# CH32V203C8U6-R0.net
KiCad netlist of a schematic drawn in Altium Designer
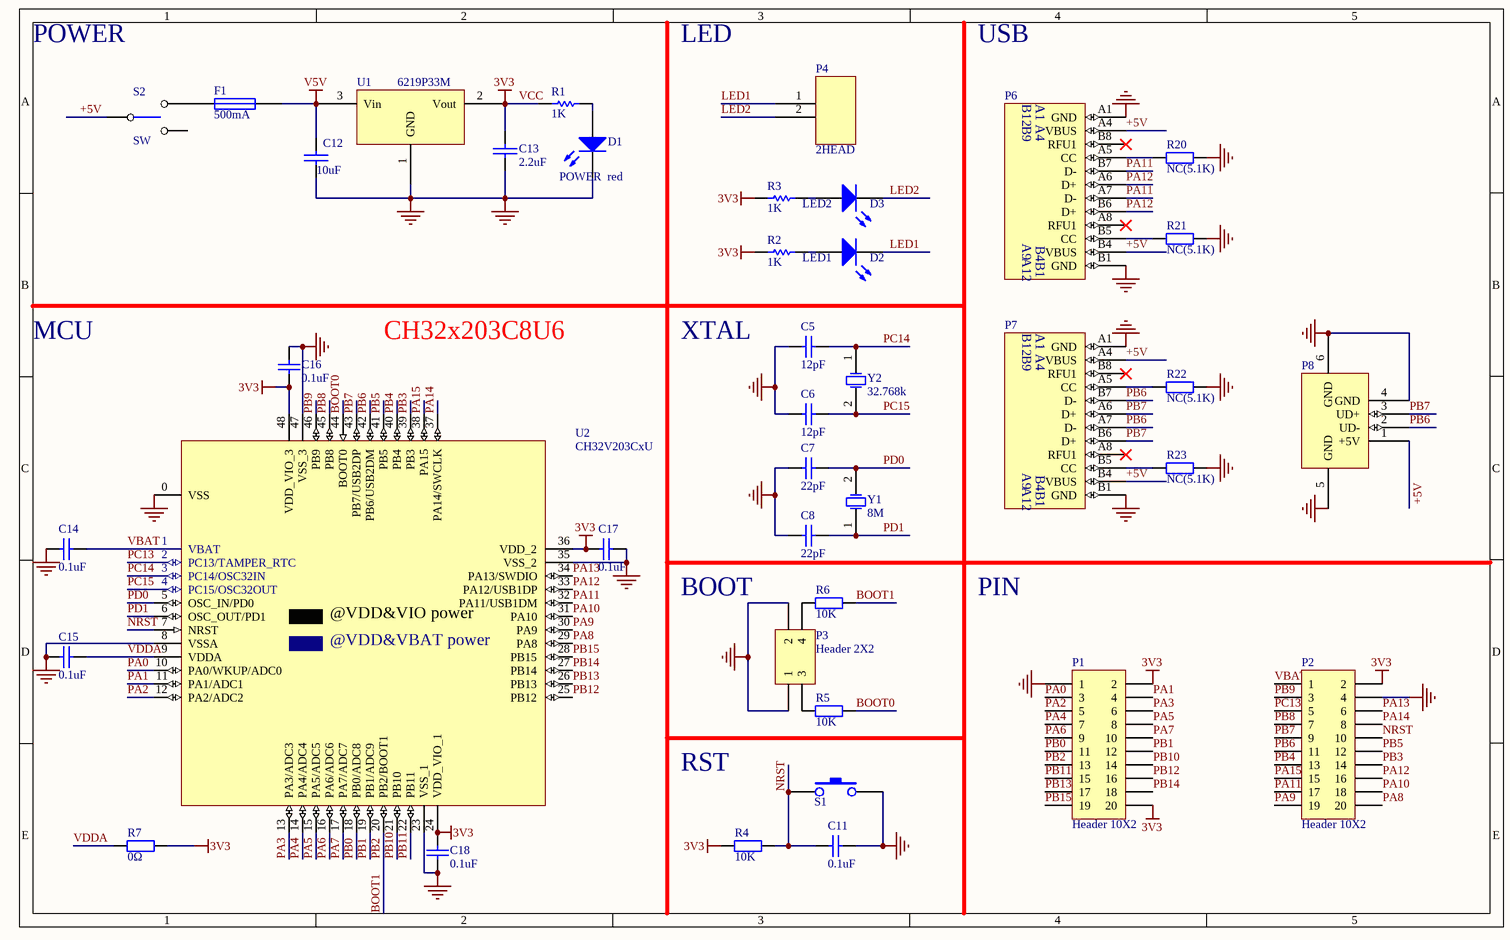
[diagram p0: CH32V203C8U6-R0.SchDoc]

(export (version "E")
  (design (tool "Eeschema 10.0.6"))
  (components
    (comp (ref "C5")
      (value "12pF")
      (footprint "0603")
      (description "Capacitor")
      (fields (field (name "PUBLISHER") "Altium Limited"))
      (libsource (lib "*") (part "Cap"))
    )
    (comp (ref "C6")
      (value "12pF")
      (footprint "0603")
      (description "Capacitor")
      (fields (field (name "PUBLISHER") "Altium Limited"))
      (libsource (lib "*") (part "Cap"))
    )
    (comp (ref "C7")
      (value "22pF")
      (footprint "0603")
      (description "Capacitor")
      (fields (field (name "PUBLISHER") "Altium Limited"))
      (libsource (lib "*") (part "Cap"))
    )
    (comp (ref "C8")
      (value "22pF")
      (footprint "0603")
      (description "Capacitor")
      (fields (field (name "PUBLISHER") "Altium Limited"))
      (libsource (lib "*") (part "Cap"))
    )
    (comp (ref "C11")
      (value "0.1uF")
      (footprint "0603")
      (description "Capacitor")
      (fields (field (name "PUBLISHER") "Altium Limited"))
      (libsource (lib "*") (part "Cap"))
    )
    (comp (ref "C12")
      (value "10uF")
      (footprint "3216")
      (description "Capacitor")
      (libsource (lib "*") (part "CAP"))
    )
    (comp (ref "C13")
      (value "2.2uF")
      (footprint "0603")
      (description "Capacitor")
      (libsource (lib "*") (part "CAP"))
    )
    (comp (ref "C14")
      (value "0.1uF")
      (footprint "0603")
      (description "Capacitor")
      (fields (field (name "PUBLISHER") "Altium Limited"))
      (libsource (lib "*") (part "Cap"))
    )
    (comp (ref "C15")
      (value "0.1uF")
      (footprint "0603")
      (description "Capacitor")
      (fields (field (name "PUBLISHER") "Altium Limited"))
      (libsource (lib "*") (part "Cap"))
    )
    (comp (ref "C16")
      (value "0.1uF")
      (footprint "0603")
      (description "Capacitor")
      (fields (field (name "PUBLISHER") "Altium Limited"))
      (libsource (lib "*") (part "Cap"))
    )
    (comp (ref "C17")
      (value "0.1uF")
      (footprint "0603")
      (description "Capacitor")
      (fields (field (name "PUBLISHER") "Altium Limited"))
      (libsource (lib "*") (part "Cap"))
    )
    (comp (ref "C18")
      (value "0.1uF")
      (footprint "0603")
      (description "Capacitor")
      (fields (field (name "PUBLISHER") "Altium Limited"))
      (libsource (lib "*") (part "Cap"))
    )
    (comp (ref "D1")
      (value "POWER  red")
      (footprint "0603L")
      (description "Typical INFRARED GaAs LED")
      (fields (field (name "PUBLISHER") "Altium Limited"))
      (libsource (lib "*") (part "LED0"))
    )
    (comp (ref "D2")
      (value "LED1")
      (footprint "0603L")
      (description "Typical INFRARED GaAs LED")
      (fields (field (name "PUBLISHER") "Altium Limited"))
      (libsource (lib "*") (part "LED0"))
    )
    (comp (ref "D3")
      (value "LED2")
      (footprint "0603L")
      (description "Typical INFRARED GaAs LED")
      (fields (field (name "PUBLISHER") "Altium Limited"))
      (libsource (lib "*") (part "LED0"))
    )
    (comp (ref "F1")
      (value "500mA")
      (footprint "0603")
      (description "Fuse")
      (libsource (lib "*") (part "FUSE1"))
    )
    (comp (ref "P1")
      (value "Header 10X2")
      (footprint "IDC20")
      (description "Header, 10-Pin, Dual row")
      (fields (field (name "PUBLISHER") "Altium Limited"))
      (libsource (lib "*") (part "Header 10X2"))
    )
    (comp (ref "P2")
      (value "Header 10X2")
      (footprint "IDC20")
      (description "Header, 10-Pin, Dual row")
      (fields (field (name "PUBLISHER") "Altium Limited"))
      (libsource (lib "*") (part "Header 10X2"))
    )
    (comp (ref "P3")
      (value "Header 2X2")
      (footprint "HDR2X2")
      (description "Header, 2-Pin, Dual row")
      (fields (field (name "PUBLISHER") "Altium Limited"))
      (libsource (lib "*") (part "Header 2X2"))
    )
    (comp (ref "P4") (value "2HEAD") (footprint "SIP2 - 40mil") (libsource (lib "*") (part "2HEAD")))
    (comp (ref "P6")
      (value "TYPE-C")
      (footprint "TYPE-C-Receptacle-2.0")
      (libsource (lib "*") (part "TYPE-C1"))
    )
    (comp (ref "P7")
      (value "TYPE-C")
      (footprint "TYPE-C-Receptacle-2.0")
      (libsource (lib "*") (part "TYPE-C1"))
    )
    (comp (ref "P8")
      (value "USB_A")
      (footprint "USBA-L")
      (description "USB Port")
      (libsource (lib "*") (part "USB"))
    )
    (comp (ref "R1")
      (value "1K")
      (footprint "0603")
      (description "Semiconductor Resistor")
      (fields (field (name "PUBLISHER") "Altium Limited"))
      (libsource (lib "*") (part "Res Semi"))
    )
    (comp (ref "R2")
      (value "1K")
      (footprint "0603")
      (description "Semiconductor Resistor")
      (fields (field (name "PUBLISHER") "Altium Limited"))
      (libsource (lib "*") (part "Res Semi"))
    )
    (comp (ref "R3")
      (value "1K")
      (footprint "0603")
      (description "Semiconductor Resistor")
      (fields (field (name "PUBLISHER") "Altium Limited"))
      (libsource (lib "*") (part "Res Semi"))
    )
    (comp (ref "R4")
      (value "10K")
      (footprint "0603")
      (description "Resistor")
      (fields (field (name "PUBLISHER") "Altium Limited"))
      (libsource (lib "*") (part "Res2"))
    )
    (comp (ref "R5")
      (value "10K")
      (footprint "0603")
      (description "Resistor")
      (fields (field (name "PUBLISHER") "Altium Limited"))
      (libsource (lib "*") (part "Res2"))
    )
    (comp (ref "R6")
      (value "10K")
      (footprint "0603")
      (description "Resistor")
      (fields (field (name "PUBLISHER") "Altium Limited"))
      (libsource (lib "*") (part "Res2"))
    )
    (comp (ref "R7")
      (value "0Ω")
      (footprint "0603")
      (description "Resistor")
      (fields (field (name "PUBLISHER") "Altium Limited"))
      (libsource (lib "*") (part "Res2"))
    )
    (comp (ref "R20")
      (value "NC(5.1K)")
      (footprint "0603")
      (description "Resistor")
      (libsource (lib "Miscellaneous Devices") (part "Res2"))
    )
    (comp (ref "R21")
      (value "NC(5.1K)")
      (footprint "0603")
      (description "Resistor")
      (libsource (lib "Miscellaneous Devices") (part "Res2"))
    )
    (comp (ref "R22")
      (value "NC(5.1K)")
      (footprint "0603")
      (description "Resistor")
      (libsource (lib "Miscellaneous Devices") (part "Res2"))
    )
    (comp (ref "R23")
      (value "NC(5.1K)")
      (footprint "0603")
      (description "Resistor")
      (libsource (lib "Miscellaneous Devices") (part "Res2"))
    )
    (comp (ref "S1") (value "KEY") (footprint "贴片按键") (libsource (lib "*") (part "KEY")))
    (comp (ref "S2") (value "SW") (footprint "KEY2") (libsource (lib "*") (part "SW")))
    (comp (ref "U1")
      (value "6219P33M")
      (footprint "SOT-23")
      (libsource (lib "wch_sch_others") (part "6219P33M"))
    )
    (comp (ref "U2")
      (value "CH32V203CxU")
      (footprint "QFN48_7X7")
      (description "RISC-V LMD-MCU, 144MHz, 2*USB FS, CAN")
      (libsource (lib "CHXXX") (part "CH32V203CxU"))
    )
    (comp (ref "Y1")
      (value "8M")
      (footprint "XT62/28")
      (description "Crystal Oscillator")
      (fields (field (name "PUBLISHER") "Altium Limited"))
      (libsource (lib "*") (part "XTAL"))
    )
    (comp (ref "Y2")
      (value "32.768k")
      (footprint "FC-135")
      (description "Crystal Oscillator")
      (fields (field (name "PUBLISHER") "Altium Limited"))
      (libsource (lib "*") (part "XTAL"))
    )
  )
  (nets
    (net (code "1") (name "/+5V") (class "Default")
      (node (ref "P6") (pin "A4") (pinfunction "VBUS_A4") (pintype "bidirectional"))
      (node (ref "P6") (pin "B4") (pinfunction "VBUS_B4") (pintype "bidirectional"))
      (node (ref "P7") (pin "A4") (pinfunction "VBUS_A4") (pintype "bidirectional"))
      (node (ref "P7") (pin "B4") (pinfunction "VBUS_B4") (pintype "bidirectional"))
      (node (ref "P8") (pin "1") (pinfunction "+5V_1") (pintype "power_in"))
      (node (ref "S2") (pin "1") (pinfunction "1_1") (pintype "passive"))
    )
    (net (code "3") (name "/BOOT0") (class "Default")
      (node (ref "R5") (pin "1") (pinfunction "1_1") (pintype "passive"))
      (node (ref "U2") (pin "44") (pinfunction "BOOT0_44") (pintype "input"))
    )
    (net (code "4") (name "/BOOT1") (class "Default")
      (node (ref "P1") (pin "13") (pinfunction "13_13") (pintype "passive"))
      (node (ref "R6") (pin "1") (pinfunction "1_1") (pintype "passive"))
      (node (ref "U2") (pin "20") (pinfunction "PB2/BOOT1_20") (pintype "bidirectional"))
    )
    (net (code "5") (name "/LED1") (class "Default")
      (node (ref "D2") (pin "2") (pinfunction "K_2") (pintype "passive"))
      (node (ref "P4") (pin "1") (pintype "passive"))
    )
    (net (code "6") (name "/LED2") (class "Default")
      (node (ref "D3") (pin "2") (pinfunction "K_2") (pintype "passive"))
      (node (ref "P4") (pin "2") (pintype "passive"))
    )
    (net (code "7") (name "/NRST") (class "Default")
      (node (ref "C11") (pin "2") (pinfunction "2_2") (pintype "passive"))
      (node (ref "P2") (pin "10") (pinfunction "10_10") (pintype "passive"))
      (node (ref "R4") (pin "1") (pinfunction "1_1") (pintype "passive"))
      (node (ref "S1") (pin "1") (pinfunction "1_1") (pintype "passive"))
      (node (ref "U2") (pin "7") (pinfunction "NRST_7") (pintype "input"))
    )
    (net (code "8") (name "/PA0") (class "Default")
      (node (ref "P1") (pin "3") (pinfunction "3_3") (pintype "passive"))
      (node (ref "U2") (pin "10") (pinfunction "PA0/WKUP/ADC0_10") (pintype "bidirectional"))
    )
    (net (code "9") (name "/PA1") (class "Default")
      (node (ref "P1") (pin "4") (pinfunction "4_4") (pintype "passive"))
      (node (ref "U2") (pin "11") (pinfunction "PA1/ADC1_11") (pintype "bidirectional"))
    )
    (net (code "10") (name "/PA2") (class "Default")
      (node (ref "P1") (pin "5") (pinfunction "5_5") (pintype "passive"))
      (node (ref "U2") (pin "12") (pinfunction "PA2/ADC2_12") (pintype "bidirectional"))
    )
    (net (code "11") (name "/PA3") (class "Default")
      (node (ref "P1") (pin "6") (pinfunction "6_6") (pintype "passive"))
      (node (ref "U2") (pin "13") (pinfunction "PA3/ADC3_13") (pintype "bidirectional"))
    )
    (net (code "12") (name "/PA4") (class "Default")
      (node (ref "P1") (pin "7") (pinfunction "7_7") (pintype "passive"))
      (node (ref "U2") (pin "14") (pinfunction "PA4/ADC4_14") (pintype "bidirectional"))
    )
    (net (code "13") (name "/PA5") (class "Default")
      (node (ref "P1") (pin "8") (pinfunction "8_8") (pintype "passive"))
      (node (ref "U2") (pin "15") (pinfunction "PA5/ADC5_15") (pintype "bidirectional"))
    )
    (net (code "14") (name "/PA6") (class "Default")
      (node (ref "P1") (pin "9") (pinfunction "9_9") (pintype "passive"))
      (node (ref "U2") (pin "16") (pinfunction "PA6/ADC6_16") (pintype "bidirectional"))
    )
    (net (code "15") (name "/PA7") (class "Default")
      (node (ref "P1") (pin "10") (pinfunction "10_10") (pintype "passive"))
      (node (ref "U2") (pin "17") (pinfunction "PA7/ADC7_17") (pintype "bidirectional"))
    )
    (net (code "16") (name "/PA8") (class "Default")
      (node (ref "P2") (pin "20") (pinfunction "20_20") (pintype "passive"))
      (node (ref "U2") (pin "29") (pinfunction "PA8_29") (pintype "bidirectional"))
    )
    (net (code "17") (name "/PA9") (class "Default")
      (node (ref "P2") (pin "19") (pinfunction "19_19") (pintype "passive"))
      (node (ref "U2") (pin "30") (pinfunction "PA9_30") (pintype "bidirectional"))
    )
    (net (code "18") (name "/PA10") (class "Default")
      (node (ref "P2") (pin "18") (pinfunction "18_18") (pintype "passive"))
      (node (ref "U2") (pin "31") (pinfunction "PA10_31") (pintype "bidirectional"))
    )
    (net (code "19") (name "/PA11") (class "Default")
      (node (ref "P2") (pin "17") (pinfunction "17_17") (pintype "passive"))
      (node (ref "P6") (pin "A7") (pinfunction "D-_A7") (pintype "bidirectional"))
      (node (ref "P6") (pin "B7") (pinfunction "D-_B7") (pintype "bidirectional"))
      (node (ref "U2") (pin "32") (pinfunction "PA11/USB1DM_32") (pintype "bidirectional"))
    )
    (net (code "20") (name "/PA12") (class "Default")
      (node (ref "P2") (pin "16") (pinfunction "16_16") (pintype "passive"))
      (node (ref "P6") (pin "A6") (pinfunction "D+_A6") (pintype "bidirectional"))
      (node (ref "P6") (pin "B6") (pinfunction "D+_B6") (pintype "bidirectional"))
      (node (ref "U2") (pin "33") (pinfunction "PA12/USB1DP_33") (pintype "bidirectional"))
    )
    (net (code "21") (name "/PA13") (class "Default")
      (node (ref "P2") (pin "6") (pinfunction "6_6") (pintype "passive"))
      (node (ref "U2") (pin "34") (pinfunction "PA13/SWDIO_34") (pintype "bidirectional"))
    )
    (net (code "22") (name "/PA14") (class "Default")
      (node (ref "P2") (pin "8") (pinfunction "8_8") (pintype "passive"))
      (node (ref "U2") (pin "37") (pinfunction "PA14/SWCLK_37") (pintype "bidirectional"))
    )
    (net (code "23") (name "/PA15") (class "Default")
      (node (ref "P2") (pin "15") (pinfunction "15_15") (pintype "passive"))
      (node (ref "U2") (pin "38") (pinfunction "PA15_38") (pintype "bidirectional"))
    )
    (net (code "24") (name "/PB0") (class "Default")
      (node (ref "P1") (pin "11") (pinfunction "11_11") (pintype "passive"))
      (node (ref "U2") (pin "18") (pinfunction "PB0/ADC8_18") (pintype "bidirectional"))
    )
    (net (code "25") (name "/PB1") (class "Default")
      (node (ref "P1") (pin "12") (pinfunction "12_12") (pintype "passive"))
      (node (ref "U2") (pin "19") (pinfunction "PB1/ADC9_19") (pintype "bidirectional"))
    )
    (net (code "26") (name "/PB3") (class "Default")
      (node (ref "P2") (pin "14") (pinfunction "14_14") (pintype "passive"))
      (node (ref "U2") (pin "39") (pinfunction "PB3_39") (pintype "bidirectional"))
    )
    (net (code "27") (name "/PB4") (class "Default")
      (node (ref "P2") (pin "13") (pinfunction "13_13") (pintype "passive"))
      (node (ref "U2") (pin "40") (pinfunction "PB4_40") (pintype "bidirectional"))
    )
    (net (code "28") (name "/PB5") (class "Default")
      (node (ref "P2") (pin "12") (pinfunction "12_12") (pintype "passive"))
      (node (ref "U2") (pin "41") (pinfunction "PB5_41") (pintype "bidirectional"))
    )
    (net (code "29") (name "/PB6") (class "Default")
      (node (ref "P2") (pin "11") (pinfunction "11_11") (pintype "passive"))
      (node (ref "P7") (pin "A7") (pinfunction "D-_A7") (pintype "bidirectional"))
      (node (ref "P7") (pin "B7") (pinfunction "D-_B7") (pintype "bidirectional"))
      (node (ref "P8") (pin "2") (pinfunction "UD-_2") (pintype "bidirectional"))
      (node (ref "U2") (pin "42") (pinfunction "PB6/USB2DM_42") (pintype "bidirectional"))
    )
    (net (code "30") (name "/PB7") (class "Default")
      (node (ref "P2") (pin "9") (pinfunction "9_9") (pintype "passive"))
      (node (ref "P7") (pin "A6") (pinfunction "D+_A6") (pintype "bidirectional"))
      (node (ref "P7") (pin "B6") (pinfunction "D+_B6") (pintype "bidirectional"))
      (node (ref "P8") (pin "3") (pinfunction "UD+_3") (pintype "bidirectional"))
      (node (ref "U2") (pin "43") (pinfunction "PB7/USB2DP_43") (pintype "bidirectional"))
    )
    (net (code "31") (name "/PB8") (class "Default")
      (node (ref "P2") (pin "7") (pinfunction "7_7") (pintype "passive"))
      (node (ref "U2") (pin "45") (pinfunction "PB8_45") (pintype "bidirectional"))
    )
    (net (code "32") (name "/PB9") (class "Default")
      (node (ref "P2") (pin "3") (pinfunction "3_3") (pintype "passive"))
      (node (ref "U2") (pin "46") (pinfunction "PB9_46") (pintype "bidirectional"))
    )
    (net (code "33") (name "/PB10") (class "Default")
      (node (ref "P1") (pin "14") (pinfunction "14_14") (pintype "passive"))
      (node (ref "U2") (pin "21") (pinfunction "PB10_21") (pintype "bidirectional"))
    )
    (net (code "34") (name "/PB11") (class "Default")
      (node (ref "P1") (pin "15") (pinfunction "15_15") (pintype "passive"))
      (node (ref "U2") (pin "22") (pinfunction "PB11_22") (pintype "bidirectional"))
    )
    (net (code "35") (name "/PB12") (class "Default")
      (node (ref "P1") (pin "16") (pinfunction "16_16") (pintype "passive"))
      (node (ref "U2") (pin "25") (pinfunction "PB12_25") (pintype "bidirectional"))
    )
    (net (code "36") (name "/PB13") (class "Default")
      (node (ref "P1") (pin "17") (pinfunction "17_17") (pintype "passive"))
      (node (ref "U2") (pin "26") (pinfunction "PB13_26") (pintype "bidirectional"))
    )
    (net (code "37") (name "/PB14") (class "Default")
      (node (ref "P1") (pin "18") (pinfunction "18_18") (pintype "passive"))
      (node (ref "U2") (pin "27") (pinfunction "PB14_27") (pintype "bidirectional"))
    )
    (net (code "38") (name "/PB15") (class "Default")
      (node (ref "P1") (pin "19") (pinfunction "19_19") (pintype "passive"))
      (node (ref "U2") (pin "28") (pinfunction "PB15_28") (pintype "bidirectional"))
    )
    (net (code "39") (name "/PC13") (class "Default")
      (node (ref "P2") (pin "5") (pinfunction "5_5") (pintype "passive"))
      (node (ref "U2") (pin "2") (pinfunction "PC13/TAMPER_RTC_2") (pintype "bidirectional"))
    )
    (net (code "40") (name "/PC14") (class "Default")
      (node (ref "C5") (pin "1") (pinfunction "1_1") (pintype "passive"))
      (node (ref "U2") (pin "3") (pinfunction "PC14/OSC32IN_3") (pintype "bidirectional"))
      (node (ref "Y2") (pin "1") (pinfunction "OSC1_1") (pintype "passive"))
    )
    (net (code "41") (name "/PC15") (class "Default")
      (node (ref "C6") (pin "1") (pinfunction "1_1") (pintype "passive"))
      (node (ref "U2") (pin "4") (pinfunction "PC15/OSC32OUT_4") (pintype "bidirectional"))
      (node (ref "Y2") (pin "2") (pinfunction "OSC2_2") (pintype "passive"))
    )
    (net (code "42") (name "/PD0") (class "Default")
      (node (ref "C7") (pin "2") (pinfunction "2_2") (pintype "passive"))
      (node (ref "U2") (pin "5") (pinfunction "OSC_IN/PD0_5") (pintype "bidirectional"))
      (node (ref "Y1") (pin "2") (pinfunction "OSC2_2") (pintype "passive"))
    )
    (net (code "43") (name "/PD1") (class "Default")
      (node (ref "C8") (pin "2") (pinfunction "2_2") (pintype "passive"))
      (node (ref "U2") (pin "6") (pinfunction "OSC_OUT/PD1_6") (pintype "bidirectional"))
      (node (ref "Y1") (pin "1") (pinfunction "OSC1_1") (pintype "passive"))
    )
    (net (code "44") (name "/VBAT") (class "Default")
      (node (ref "C14") (pin "1") (pinfunction "1_1") (pintype "passive"))
      (node (ref "P2") (pin "1") (pinfunction "1_1") (pintype "passive"))
      (node (ref "U2") (pin "1") (pinfunction "VBAT_1") (pintype "power_in"))
    )
    (net (code "45") (name "/VDDA") (class "Default")
      (node (ref "C15") (pin "1") (pinfunction "1_1") (pintype "passive"))
      (node (ref "R7") (pin "2") (pinfunction "2_2") (pintype "passive"))
      (node (ref "U2") (pin "9") (pinfunction "VDDA_9") (pintype "power_in"))
    )
    (net (code "46") (name "3V3") (class "Default")
      (node (ref "C13") (pin "1") (pinfunction "1_1") (pintype "passive"))
      (node (ref "C16") (pin "2") (pinfunction "2_2") (pintype "passive"))
      (node (ref "C17") (pin "2") (pinfunction "2_2") (pintype "passive"))
      (node (ref "C18") (pin "2") (pinfunction "2_2") (pintype "passive"))
      (node (ref "P1") (pin "2") (pinfunction "2_2") (pintype "passive"))
      (node (ref "P1") (pin "20") (pinfunction "20_20") (pintype "passive"))
      (node (ref "P2") (pin "2") (pinfunction "2_2") (pintype "passive"))
      (node (ref "R1") (pin "2") (pinfunction "2_2") (pintype "passive"))
      (node (ref "R2") (pin "1") (pinfunction "1_1") (pintype "passive"))
      (node (ref "R3") (pin "1") (pinfunction "1_1") (pintype "passive"))
      (node (ref "R4") (pin "2") (pinfunction "2_2") (pintype "passive"))
      (node (ref "R7") (pin "1") (pinfunction "1_1") (pintype "passive"))
      (node (ref "U1") (pin "2") (pinfunction "Vout_2") (pintype "passive"))
      (node (ref "U2") (pin "24") (pinfunction "VDD_VIO_1_24") (pintype "power_in"))
      (node (ref "U2") (pin "36") (pinfunction "VDD_2_36") (pintype "power_in"))
      (node (ref "U2") (pin "48") (pinfunction "VDD_VIO_3_48") (pintype "power_in"))
    )
    (net (code "47") (name "GND") (class "Default")
      (node (ref "C11") (pin "1") (pinfunction "1_1") (pintype "passive"))
      (node (ref "C12") (pin "2") (pinfunction "2_2") (pintype "passive"))
      (node (ref "C13") (pin "2") (pinfunction "2_2") (pintype "passive"))
      (node (ref "C14") (pin "2") (pinfunction "2_2") (pintype "passive"))
      (node (ref "C15") (pin "2") (pinfunction "2_2") (pintype "passive"))
      (node (ref "C16") (pin "1") (pinfunction "1_1") (pintype "passive"))
      (node (ref "C17") (pin "1") (pinfunction "1_1") (pintype "passive"))
      (node (ref "C18") (pin "1") (pinfunction "1_1") (pintype "passive"))
      (node (ref "C5") (pin "2") (pinfunction "2_2") (pintype "passive"))
      (node (ref "C6") (pin "2") (pinfunction "2_2") (pintype "passive"))
      (node (ref "C7") (pin "1") (pinfunction "1_1") (pintype "passive"))
      (node (ref "C8") (pin "1") (pinfunction "1_1") (pintype "passive"))
      (node (ref "D1") (pin "2") (pinfunction "K_2") (pintype "passive"))
      (node (ref "P1") (pin "1") (pinfunction "1_1") (pintype "passive"))
      (node (ref "P2") (pin "4") (pinfunction "4_4") (pintype "passive"))
      (node (ref "P3") (pin "1") (pinfunction "1_1") (pintype "passive"))
      (node (ref "P3") (pin "2") (pinfunction "2_2") (pintype "passive"))
      (node (ref "P6") (pin "A1") (pinfunction "GND_A1") (pintype "bidirectional"))
      (node (ref "P6") (pin "B1") (pinfunction "GND_B1") (pintype "bidirectional"))
      (node (ref "P7") (pin "A1") (pinfunction "GND_A1") (pintype "bidirectional"))
      (node (ref "P7") (pin "B1") (pinfunction "GND_B1") (pintype "bidirectional"))
      (node (ref "P8") (pin "4") (pinfunction "GND_4") (pintype "power_in"))
      (node (ref "P8") (pin "5") (pinfunction "GND_5") (pintype "power_in"))
      (node (ref "P8") (pin "6") (pinfunction "GND_6") (pintype "power_in"))
      (node (ref "R20") (pin "2") (pinfunction "2_2") (pintype "passive"))
      (node (ref "R21") (pin "2") (pinfunction "2_2") (pintype "passive"))
      (node (ref "R22") (pin "2") (pinfunction "2_2") (pintype "passive"))
      (node (ref "R23") (pin "2") (pinfunction "2_2") (pintype "passive"))
      (node (ref "S1") (pin "3") (pinfunction "3_3") (pintype "passive"))
      (node (ref "U1") (pin "1") (pinfunction "GND_1") (pintype "passive"))
      (node (ref "U2") (pin "0") (pinfunction "VSS_0") (pintype "power_in"))
      (node (ref "U2") (pin "23") (pinfunction "VSS_1_23") (pintype "power_in"))
      (node (ref "U2") (pin "35") (pinfunction "VSS_2_35") (pintype "power_in"))
      (node (ref "U2") (pin "47") (pinfunction "VSS_3_47") (pintype "power_in"))
      (node (ref "U2") (pin "8") (pinfunction "VSSA_8") (pintype "power_in"))
    )
    (net (code "48") (name "Net-(D1-A)") (class "Default")
      (node (ref "D1") (pin "1") (pinfunction "A_1") (pintype "passive"))
      (node (ref "R1") (pin "1") (pinfunction "1_1") (pintype "passive"))
    )
    (net (code "49") (name "Net-(D2-A)") (class "Default")
      (node (ref "D2") (pin "1") (pinfunction "A_1") (pintype "passive"))
      (node (ref "R2") (pin "2") (pinfunction "2_2") (pintype "passive"))
    )
    (net (code "50") (name "Net-(D3-A)") (class "Default")
      (node (ref "D3") (pin "1") (pinfunction "A_1") (pintype "passive"))
      (node (ref "R3") (pin "2") (pinfunction "2_2") (pintype "passive"))
    )
    (net (code "51") (name "Net-(F1-Pad1)") (class "Default")
      (node (ref "F1") (pin "1") (pinfunction "1_1") (pintype "passive"))
      (node (ref "S2") (pin "3") (pinfunction "3_3") (pintype "passive"))
    )
    (net (code "52") (name "Net-(P3-Pad3)") (class "Default")
      (node (ref "P3") (pin "3") (pinfunction "3_3") (pintype "passive"))
      (node (ref "R5") (pin "2") (pinfunction "2_2") (pintype "passive"))
    )
    (net (code "53") (name "Net-(P3-Pad4)") (class "Default")
      (node (ref "P3") (pin "4") (pinfunction "4_4") (pintype "passive"))
      (node (ref "R6") (pin "2") (pinfunction "2_2") (pintype "passive"))
    )
    (net (code "54") (name "Net-(P6-CC-PadA5)") (class "Default")
      (node (ref "P6") (pin "A5") (pinfunction "CC_A5") (pintype "bidirectional"))
      (node (ref "R20") (pin "1") (pinfunction "1_1") (pintype "passive"))
    )
    (net (code "55") (name "Net-(P6-CC-PadB5)") (class "Default")
      (node (ref "P6") (pin "B5") (pinfunction "CC_B5") (pintype "bidirectional"))
      (node (ref "R21") (pin "1") (pinfunction "1_1") (pintype "passive"))
    )
    (net (code "56") (name "Net-(P7-CC-PadA5)") (class "Default")
      (node (ref "P7") (pin "A5") (pinfunction "CC_A5") (pintype "bidirectional"))
      (node (ref "R22") (pin "1") (pinfunction "1_1") (pintype "passive"))
    )
    (net (code "57") (name "Net-(P7-CC-PadB5)") (class "Default")
      (node (ref "P7") (pin "B5") (pinfunction "CC_B5") (pintype "bidirectional"))
      (node (ref "R23") (pin "1") (pinfunction "1_1") (pintype "passive"))
    )
    (net (code "58") (name "V5V") (class "Default")
      (node (ref "C12") (pin "1") (pinfunction "1_1") (pintype "passive"))
      (node (ref "F1") (pin "2") (pinfunction "2_2") (pintype "passive"))
      (node (ref "U1") (pin "3") (pinfunction "Vin_3") (pintype "passive"))
    )
    (net (code "59") (name "unconnected-(P6-RFU1-PadA8)") (class "Default")
      (node (ref "P6") (pin "A8") (pinfunction "RFU1_A8") (pintype "bidirectional+no_connect"))
    )
    (net (code "60") (name "unconnected-(P6-RFU1-PadB8)") (class "Default")
      (node (ref "P6") (pin "B8") (pinfunction "RFU1_B8") (pintype "bidirectional+no_connect"))
    )
    (net (code "61") (name "unconnected-(P7-RFU1-PadA8)") (class "Default")
      (node (ref "P7") (pin "A8") (pinfunction "RFU1_A8") (pintype "bidirectional+no_connect"))
    )
    (net (code "62") (name "unconnected-(P7-RFU1-PadB8)") (class "Default")
      (node (ref "P7") (pin "B8") (pinfunction "RFU1_B8") (pintype "bidirectional+no_connect"))
    )
    (net (code "63") (name "unconnected-(S2-Pad2)") (class "Default")
      (node (ref "S2") (pin "2") (pinfunction "2_2") (pintype "passive"))
    )
  )
)
